# Flat_Back_Eurorack_Busboard_Small.net
KiCad netlist of a schematic drawn in EAGLE
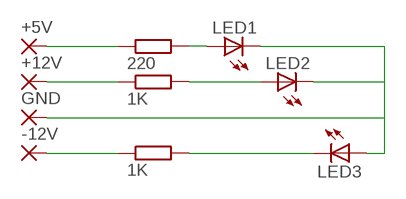
[diagram p0: schematic, sheet 1]

(export (version "E")
  (design (tool "Eeschema 10.0.6"))
  (components
    (comp (ref "+5V")
      (value "SMD5")
      (footprint "eagle-import:SMD2,54-5,08")
      (libsource (lib "eagle-import") (part "SMD5"))
    )
    (comp (ref "+12V")
      (value "SMD5")
      (footprint "eagle-import:SMD2,54-5,08")
      (libsource (lib "eagle-import") (part "SMD5"))
    )
    (comp (ref "-12V")
      (value "SMD5")
      (footprint "eagle-import:SMD2,54-5,08")
      (libsource (lib "eagle-import") (part "SMD5"))
    )
    (comp (ref "GND")
      (value "SMD5")
      (footprint "eagle-import:SMD2,54-5,08")
      (libsource (lib "eagle-import") (part "SMD5"))
    )
    (comp (ref "LED1")
      (value "LEDCHIPLED_0805")
      (footprint "eagle-import:CHIPLED_0805")
      (libsource (lib "eagle-import") (part "LEDCHIPLED_0805"))
    )
    (comp (ref "LED2")
      (value "LEDCHIPLED_0805")
      (footprint "eagle-import:CHIPLED_0805")
      (libsource (lib "eagle-import") (part "LEDCHIPLED_0805"))
    )
    (comp (ref "LED3")
      (value "LEDCHIPLED_0805")
      (footprint "eagle-import:CHIPLED_0805")
      (libsource (lib "eagle-import") (part "LEDCHIPLED_0805"))
    )
    (comp (ref "R1")
      (value "220")
      (footprint "eagle-import:M0805")
      (libsource (lib "eagle-import") (part "R-EU_M0805"))
    )
    (comp (ref "R2")
      (value "1K")
      (footprint "eagle-import:M0805")
      (libsource (lib "eagle-import") (part "R-EU_M0805"))
    )
    (comp (ref "R3")
      (value "1K")
      (footprint "eagle-import:M0805")
      (libsource (lib "eagle-import") (part "R-EU_M0805"))
    )
  )
  (nets
    (net (code "1") (name "Net-(+5V-P)") (class "Default")
      (node (ref "+5V") (pin "1") (pinfunction "P_1") (pintype "passive"))
      (node (ref "R1") (pin "1") (pinfunction "1_1") (pintype "passive"))
    )
    (net (code "2") (name "Net-(+12V-P)") (class "Default")
      (node (ref "+12V") (pin "1") (pinfunction "P_1") (pintype "passive"))
      (node (ref "R2") (pin "1") (pinfunction "1_1") (pintype "passive"))
    )
    (net (code "3") (name "Net-(-12V-P)") (class "Default")
      (node (ref "-12V") (pin "1") (pinfunction "P_1") (pintype "passive"))
      (node (ref "R3") (pin "1") (pinfunction "1_1") (pintype "passive"))
    )
    (net (code "4") (name "Net-(GND-P)") (class "Default")
      (node (ref "GND") (pin "1") (pinfunction "P_1") (pintype "passive"))
      (node (ref "LED1") (pin "C") (pinfunction "C_C") (pintype "passive"))
      (node (ref "LED2") (pin "C") (pinfunction "C_C") (pintype "passive"))
      (node (ref "LED3") (pin "A") (pinfunction "A_A") (pintype "passive"))
    )
    (net (code "5") (name "Net-(LED1-PadA)") (class "Default")
      (node (ref "LED1") (pin "A") (pinfunction "A_A") (pintype "passive"))
      (node (ref "R1") (pin "2") (pinfunction "2_2") (pintype "passive"))
    )
    (net (code "6") (name "Net-(LED2-PadA)") (class "Default")
      (node (ref "LED2") (pin "A") (pinfunction "A_A") (pintype "passive"))
      (node (ref "R2") (pin "2") (pinfunction "2_2") (pintype "passive"))
    )
    (net (code "7") (name "Net-(LED3-PadC)") (class "Default")
      (node (ref "LED3") (pin "C") (pinfunction "C_C") (pintype "passive"))
      (node (ref "R3") (pin "2") (pinfunction "2_2") (pintype "passive"))
    )
  )
)
